# timer555.net
KiCad netlist of a schematic drawn in EAGLE
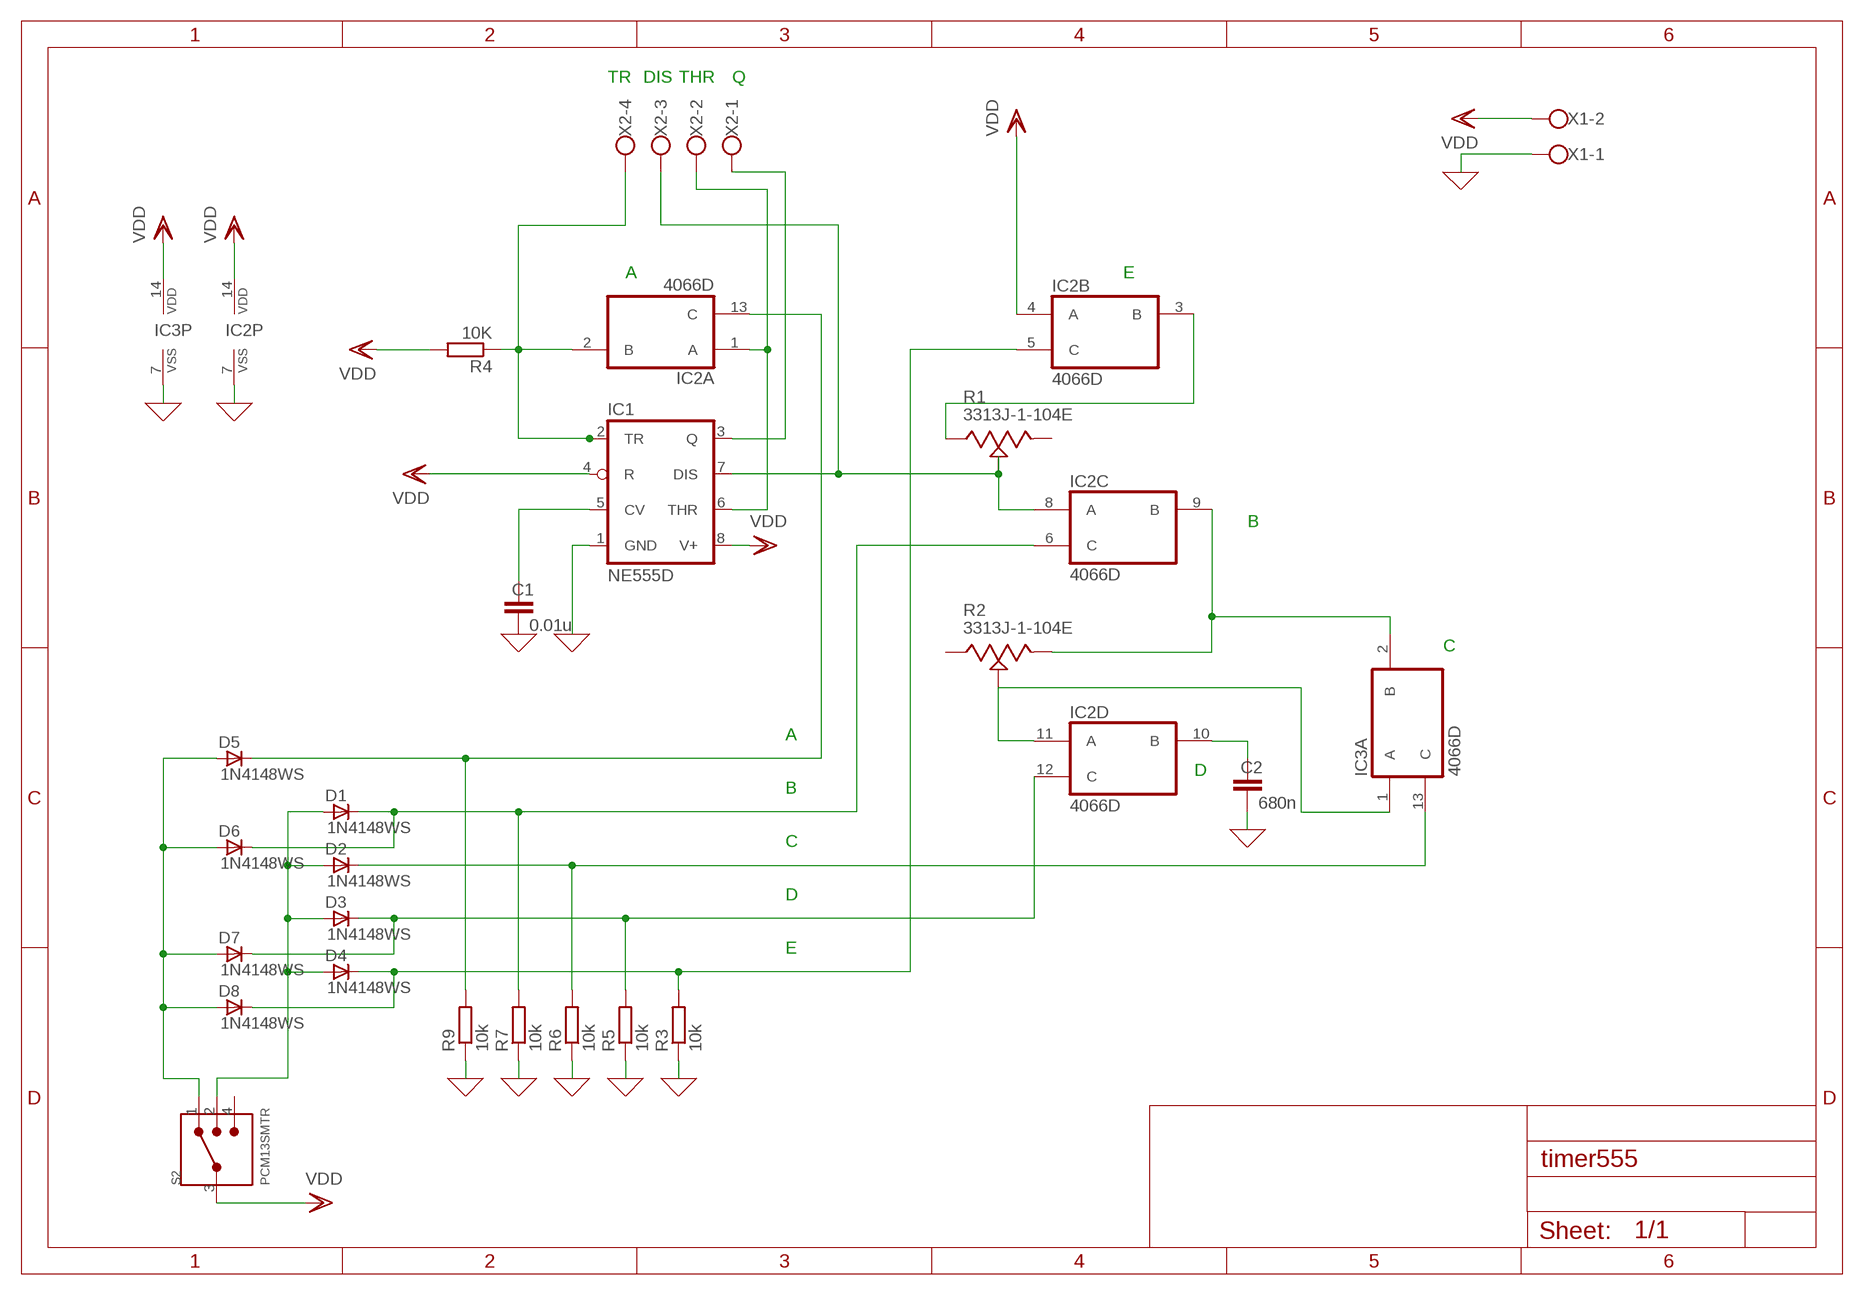
[diagram p0: schematic, sheet 1]

(export (version "E")
  (design (tool "Eeschema 10.0.6"))
  (components
    (comp (ref "C1")
      (value "0.01u")
      (footprint "eagle-import:C0805")
      (libsource (lib "eagle-import") (part "C-EUC0805"))
    )
    (comp (ref "C2")
      (value "680n")
      (footprint "eagle-import:C0805")
      (libsource (lib "eagle-import") (part "C-EUC0805"))
    )
    (comp (ref "D1")
      (value "1N4148WS")
      (footprint "eagle-import:SOD323F")
      (libsource (lib "eagle-import") (part "1N4148WS"))
    )
    (comp (ref "D2")
      (value "1N4148WS")
      (footprint "eagle-import:SOD323F")
      (libsource (lib "eagle-import") (part "1N4148WS"))
    )
    (comp (ref "D3")
      (value "1N4148WS")
      (footprint "eagle-import:SOD323F")
      (libsource (lib "eagle-import") (part "1N4148WS"))
    )
    (comp (ref "D4")
      (value "1N4148WS")
      (footprint "eagle-import:SOD323F")
      (libsource (lib "eagle-import") (part "1N4148WS"))
    )
    (comp (ref "D5")
      (value "1N4148WS")
      (footprint "eagle-import:SOD323F")
      (libsource (lib "eagle-import") (part "1N4148WS"))
    )
    (comp (ref "D6")
      (value "1N4148WS")
      (footprint "eagle-import:SOD323F")
      (libsource (lib "eagle-import") (part "1N4148WS"))
    )
    (comp (ref "D7")
      (value "1N4148WS")
      (footprint "eagle-import:SOD323F")
      (libsource (lib "eagle-import") (part "1N4148WS"))
    )
    (comp (ref "D8")
      (value "1N4148WS")
      (footprint "eagle-import:SOD323F")
      (libsource (lib "eagle-import") (part "1N4148WS"))
    )
    (comp (ref "IC1")
      (value "NE555D")
      (footprint "eagle-import:SO08")
      (libsource (lib "eagle-import") (part "555DNE"))
    )
    (comp (ref "IC2")
      (value "4066D")
      (footprint "eagle-import:SO14")
      (libsource (lib "eagle-import") (part "4066D"))
    )
    (comp (ref "IC3")
      (value "4066D")
      (footprint "eagle-import:SO14")
      (libsource (lib "eagle-import") (part "4066D"))
    )
    (comp (ref "R1")
      (value "3313J-1-104E")
      (footprint "eagle-import:TRIM_3313J-1-104E")
      (fields (field (name "DIGI-KEY_PART_NUMBER") "3313J-104ECT-ND") (field (name "MF") "Bourns"))
      (libsource (lib "eagle-import") (part "3313J-1-104E"))
    )
    (comp (ref "R2")
      (value "3313J-1-104E")
      (footprint "eagle-import:TRIM_3313J-1-104E")
      (fields (field (name "DIGI-KEY_PART_NUMBER") "3313J-104ECT-ND") (field (name "MF") "Bourns"))
      (libsource (lib "eagle-import") (part "3313J-1-104E"))
    )
    (comp (ref "R3")
      (value "10k")
      (footprint "eagle-import:R0805")
      (libsource (lib "eagle-import") (part "R-EU_R0805"))
    )
    (comp (ref "R4")
      (value "10K")
      (footprint "eagle-import:R0805")
      (libsource (lib "eagle-import") (part "R-EU_R0805"))
    )
    (comp (ref "R5")
      (value "10k")
      (footprint "eagle-import:R0805")
      (libsource (lib "eagle-import") (part "R-EU_R0805"))
    )
    (comp (ref "R6")
      (value "10k")
      (footprint "eagle-import:R0805")
      (libsource (lib "eagle-import") (part "R-EU_R0805"))
    )
    (comp (ref "R7")
      (value "10k")
      (footprint "eagle-import:R0805")
      (libsource (lib "eagle-import") (part "R-EU_R0805"))
    )
    (comp (ref "R9")
      (value "10k")
      (footprint "eagle-import:R0805")
      (libsource (lib "eagle-import") (part "R-EU_R0805"))
    )
    (comp (ref "S2")
      (value "PCM13SMTR")
      (footprint "eagle-import:SW_PCM13SMTR")
      (fields (field (name "MF") "C&K"))
      (libsource (lib "eagle-import") (part "PCM13SMTR"))
    )
    (comp (ref "X1")
      (value "W237-102")
      (footprint "eagle-import:W237-102")
      (fields (field (name "MPN") "237-102"))
      (libsource (lib "eagle-import") (part "W237-102"))
    )
    (comp (ref "X2")
      (value "W237-4")
      (footprint "eagle-import:W237-4")
      (libsource (lib "eagle-import") (part "W237-4"))
    )
  )
  (nets
    (net (code "1") (name "GND") (class "Default")
      (node (ref "C1") (pin "2") (pinfunction "2_2") (pintype "passive"))
      (node (ref "C2") (pin "2") (pinfunction "2_2") (pintype "passive"))
      (node (ref "IC1") (pin "1") (pinfunction "GND_1") (pintype "power_in"))
      (node (ref "IC2") (pin "7") (pinfunction "VSS_7") (pintype "power_in"))
      (node (ref "IC3") (pin "7") (pinfunction "VSS_7") (pintype "power_in"))
      (node (ref "R3") (pin "1") (pinfunction "1_1") (pintype "passive"))
      (node (ref "R5") (pin "1") (pinfunction "1_1") (pintype "passive"))
      (node (ref "R6") (pin "1") (pinfunction "1_1") (pintype "passive"))
      (node (ref "R7") (pin "1") (pinfunction "1_1") (pintype "passive"))
      (node (ref "R9") (pin "1") (pinfunction "1_1") (pintype "passive"))
      (node (ref "X1") (pin "1") (pinfunction "KL_1") (pintype "passive"))
    )
    (net (code "2") (name "Net-(D1-PadA)") (class "Default")
      (node (ref "D1") (pin "A") (pinfunction "A_A") (pintype "passive"))
      (node (ref "D2") (pin "A") (pinfunction "A_A") (pintype "passive"))
      (node (ref "D3") (pin "A") (pinfunction "A_A") (pintype "passive"))
      (node (ref "D4") (pin "A") (pinfunction "A_A") (pintype "passive"))
      (node (ref "S2") (pin "2") (pinfunction "2_2") (pintype "passive"))
    )
    (net (code "3") (name "Net-(D5-PadA)") (class "Default")
      (node (ref "D5") (pin "A") (pinfunction "A_A") (pintype "passive"))
      (node (ref "D6") (pin "A") (pinfunction "A_A") (pintype "passive"))
      (node (ref "D7") (pin "A") (pinfunction "A_A") (pintype "passive"))
      (node (ref "D8") (pin "A") (pinfunction "A_A") (pintype "passive"))
      (node (ref "S2") (pin "1") (pinfunction "1_1") (pintype "passive"))
    )
    (net (code "4") (name "Net-(IC1-CV)") (class "Default")
      (node (ref "C1") (pin "1") (pinfunction "1_1") (pintype "passive"))
      (node (ref "IC1") (pin "5") (pinfunction "CV_5") (pintype "input"))
    )
    (net (code "5") (name "Net-(IC1-DIS)") (class "Default")
      (node (ref "IC1") (pin "7") (pinfunction "DIS_7") (pintype "input"))
      (node (ref "IC2") (pin "8") (pinfunction "A_8") (pintype "tri_state"))
      (node (ref "R1") (pin "2") (pinfunction "WIPER_2") (pintype "passive"))
      (node (ref "X2") (pin "3") (pinfunction "KL_3") (pintype "passive"))
    )
    (net (code "6") (name "Net-(IC1-Q)") (class "Default")
      (node (ref "IC1") (pin "3") (pinfunction "Q_3") (pintype "output"))
      (node (ref "X2") (pin "1") (pinfunction "KL_1") (pintype "passive"))
    )
    (net (code "7") (name "Net-(IC1-THR)") (class "Default")
      (node (ref "IC1") (pin "6") (pinfunction "THR_6") (pintype "input"))
      (node (ref "IC2") (pin "1") (pinfunction "A_1") (pintype "tri_state"))
      (node (ref "X2") (pin "2") (pinfunction "KL_2") (pintype "passive"))
    )
    (net (code "8") (name "Net-(IC1-TR)") (class "Default")
      (node (ref "IC1") (pin "2") (pinfunction "TR_2") (pintype "input"))
      (node (ref "IC2") (pin "2") (pinfunction "B_2") (pintype "tri_state"))
      (node (ref "R4") (pin "1") (pinfunction "1_1") (pintype "passive"))
      (node (ref "X2") (pin "4") (pinfunction "KL_4") (pintype "passive"))
    )
    (net (code "9") (name "Net-(IC2A-C)") (class "Default")
      (node (ref "D5") (pin "C") (pinfunction "C_C") (pintype "passive"))
      (node (ref "IC2") (pin "13") (pinfunction "C_13") (pintype "input"))
      (node (ref "R9") (pin "2") (pinfunction "2_2") (pintype "passive"))
    )
    (net (code "10") (name "Net-(IC2B-B)") (class "Default")
      (node (ref "IC2") (pin "3") (pinfunction "B_3") (pintype "tri_state"))
      (node (ref "R1") (pin "1") (pinfunction "CCW_1") (pintype "passive"))
    )
    (net (code "11") (name "Net-(IC2B-C)") (class "Default")
      (node (ref "D4") (pin "C") (pinfunction "C_C") (pintype "passive"))
      (node (ref "D8") (pin "C") (pinfunction "C_C") (pintype "passive"))
      (node (ref "IC2") (pin "5") (pinfunction "C_5") (pintype "input"))
      (node (ref "R3") (pin "2") (pinfunction "2_2") (pintype "passive"))
    )
    (net (code "12") (name "Net-(IC2C-B)") (class "Default")
      (node (ref "IC2") (pin "9") (pinfunction "B_9") (pintype "tri_state"))
      (node (ref "IC3") (pin "2") (pinfunction "B_2") (pintype "tri_state"))
      (node (ref "R2") (pin "3") (pinfunction "CW_3") (pintype "passive"))
    )
    (net (code "13") (name "Net-(IC2C-C)") (class "Default")
      (node (ref "D1") (pin "C") (pinfunction "C_C") (pintype "passive"))
      (node (ref "D6") (pin "C") (pinfunction "C_C") (pintype "passive"))
      (node (ref "IC2") (pin "6") (pinfunction "C_6") (pintype "input"))
      (node (ref "R7") (pin "2") (pinfunction "2_2") (pintype "passive"))
    )
    (net (code "14") (name "Net-(IC2D-A)") (class "Default")
      (node (ref "IC2") (pin "11") (pinfunction "A_11") (pintype "tri_state"))
      (node (ref "IC3") (pin "1") (pinfunction "A_1") (pintype "tri_state"))
      (node (ref "R2") (pin "2") (pinfunction "WIPER_2") (pintype "passive"))
    )
    (net (code "15") (name "Net-(IC2D-B)") (class "Default")
      (node (ref "C2") (pin "1") (pinfunction "1_1") (pintype "passive"))
      (node (ref "IC2") (pin "10") (pinfunction "B_10") (pintype "tri_state"))
    )
    (net (code "16") (name "Net-(IC2D-C)") (class "Default")
      (node (ref "D3") (pin "C") (pinfunction "C_C") (pintype "passive"))
      (node (ref "D7") (pin "C") (pinfunction "C_C") (pintype "passive"))
      (node (ref "IC2") (pin "12") (pinfunction "C_12") (pintype "input"))
      (node (ref "R5") (pin "2") (pinfunction "2_2") (pintype "passive"))
    )
    (net (code "17") (name "Net-(IC3A-C)") (class "Default")
      (node (ref "D2") (pin "C") (pinfunction "C_C") (pintype "passive"))
      (node (ref "IC3") (pin "13") (pinfunction "C_13") (pintype "input"))
      (node (ref "R6") (pin "2") (pinfunction "2_2") (pintype "passive"))
    )
    (net (code "18") (name "VDD") (class "Default")
      (node (ref "IC1") (pin "4") (pinfunction "R_4") (pintype "input"))
      (node (ref "IC1") (pin "8") (pinfunction "V+_8") (pintype "power_in"))
      (node (ref "IC2") (pin "14") (pinfunction "VDD_14") (pintype "power_in"))
      (node (ref "IC2") (pin "4") (pinfunction "A_4") (pintype "tri_state"))
      (node (ref "IC3") (pin "14") (pinfunction "VDD_14") (pintype "power_in"))
      (node (ref "R4") (pin "2") (pinfunction "2_2") (pintype "passive"))
      (node (ref "S2") (pin "3") (pinfunction "3_3") (pintype "passive"))
      (node (ref "X1") (pin "2") (pinfunction "KL_2") (pintype "passive"))
    )
    (net (code "19") (name "unconnected-(R1-CW-Pad3)") (class "Default")
      (node (ref "R1") (pin "3") (pinfunction "CW_3") (pintype "passive"))
    )
    (net (code "20") (name "unconnected-(R2-CCW-Pad1)") (class "Default")
      (node (ref "R2") (pin "1") (pinfunction "CCW_1") (pintype "passive"))
    )
    (net (code "21") (name "unconnected-(S2-Pad4)") (class "Default")
      (node (ref "S2") (pin "4") (pinfunction "4_4") (pintype "passive"))
    )
  )
)
